# beaglebone_rotor_control_cape.net
KiCad netlist of a schematic drawn in EAGLE
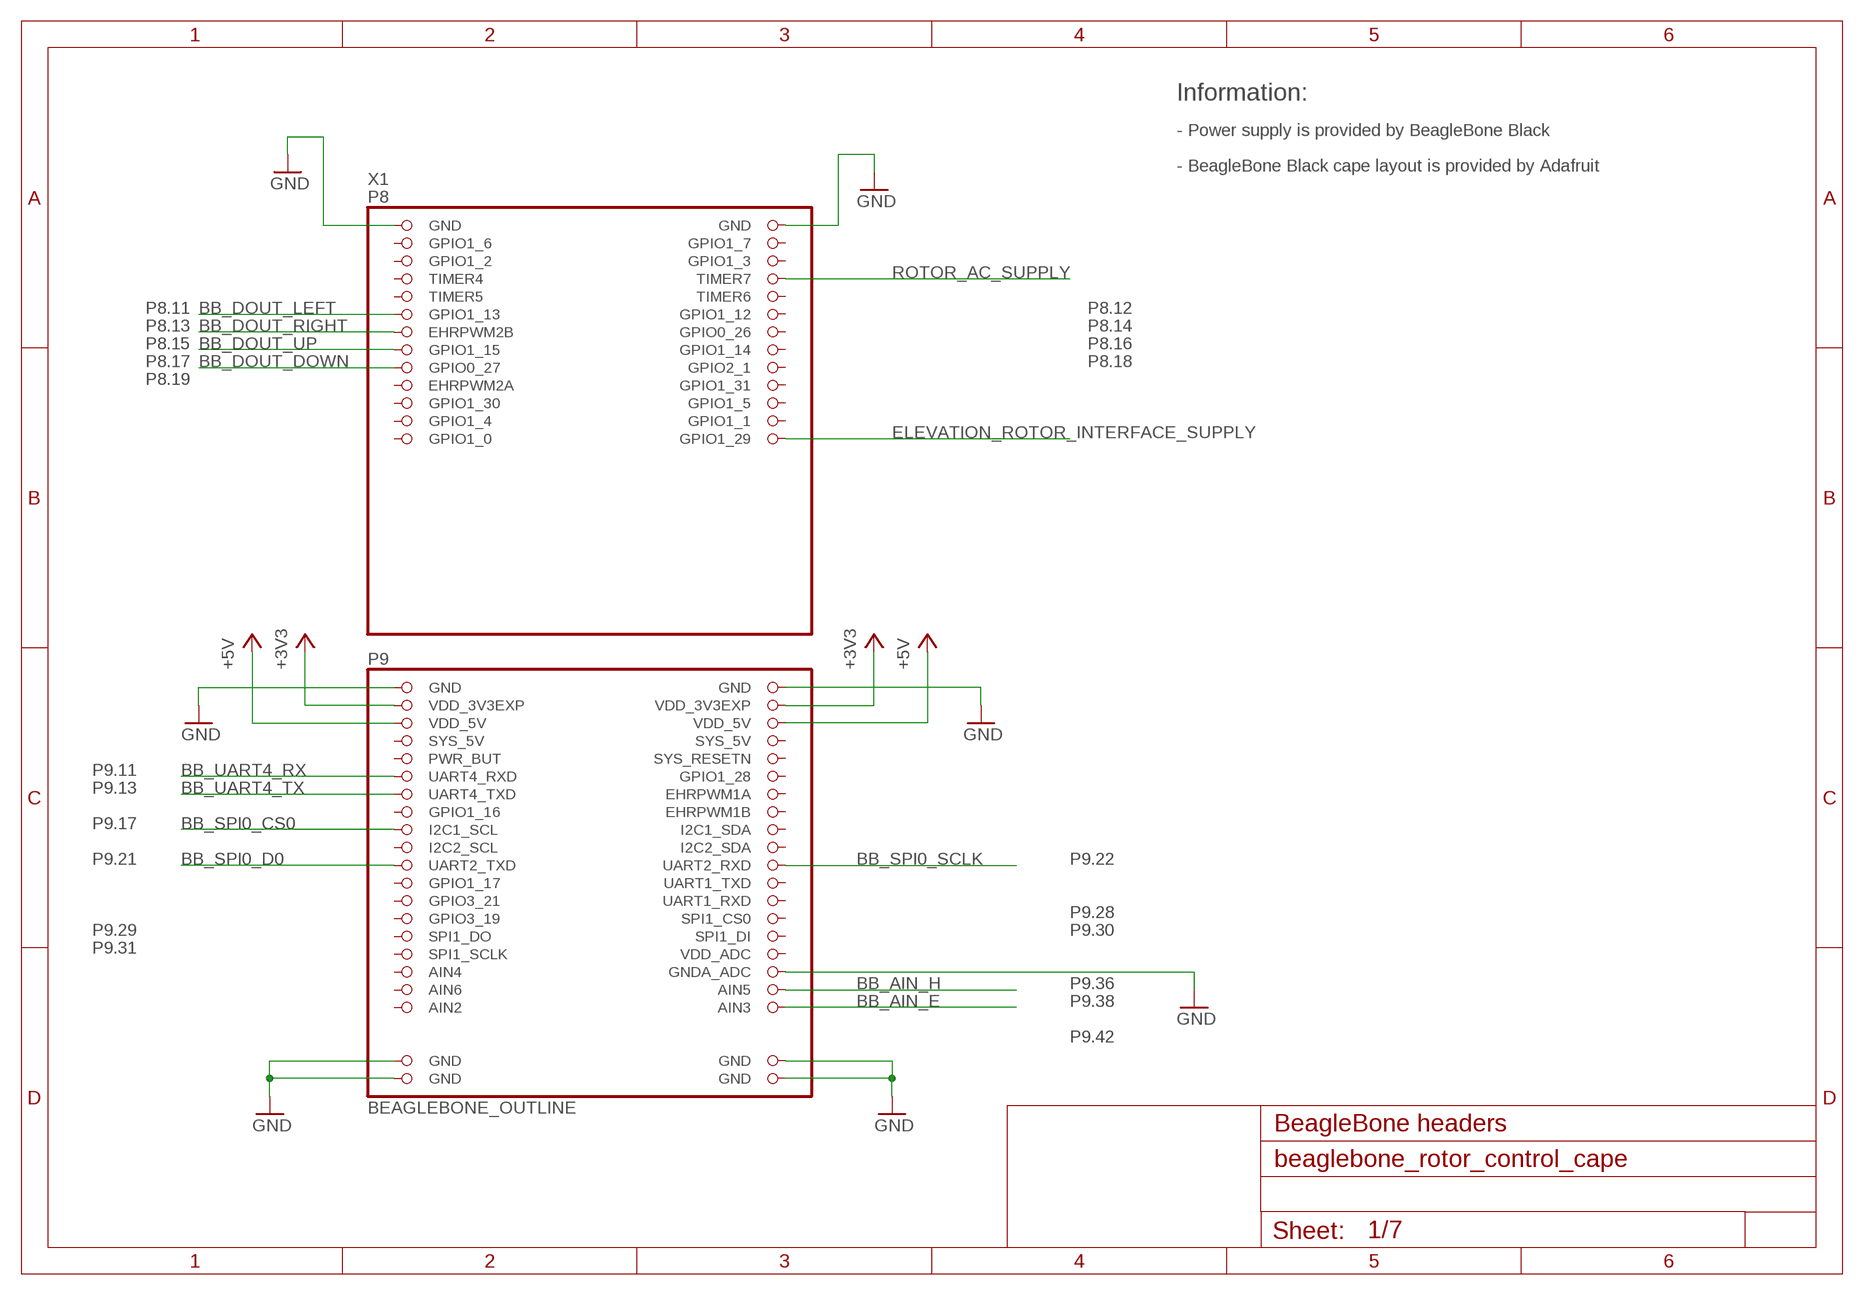
[diagram p0: schematic, sheet 1]
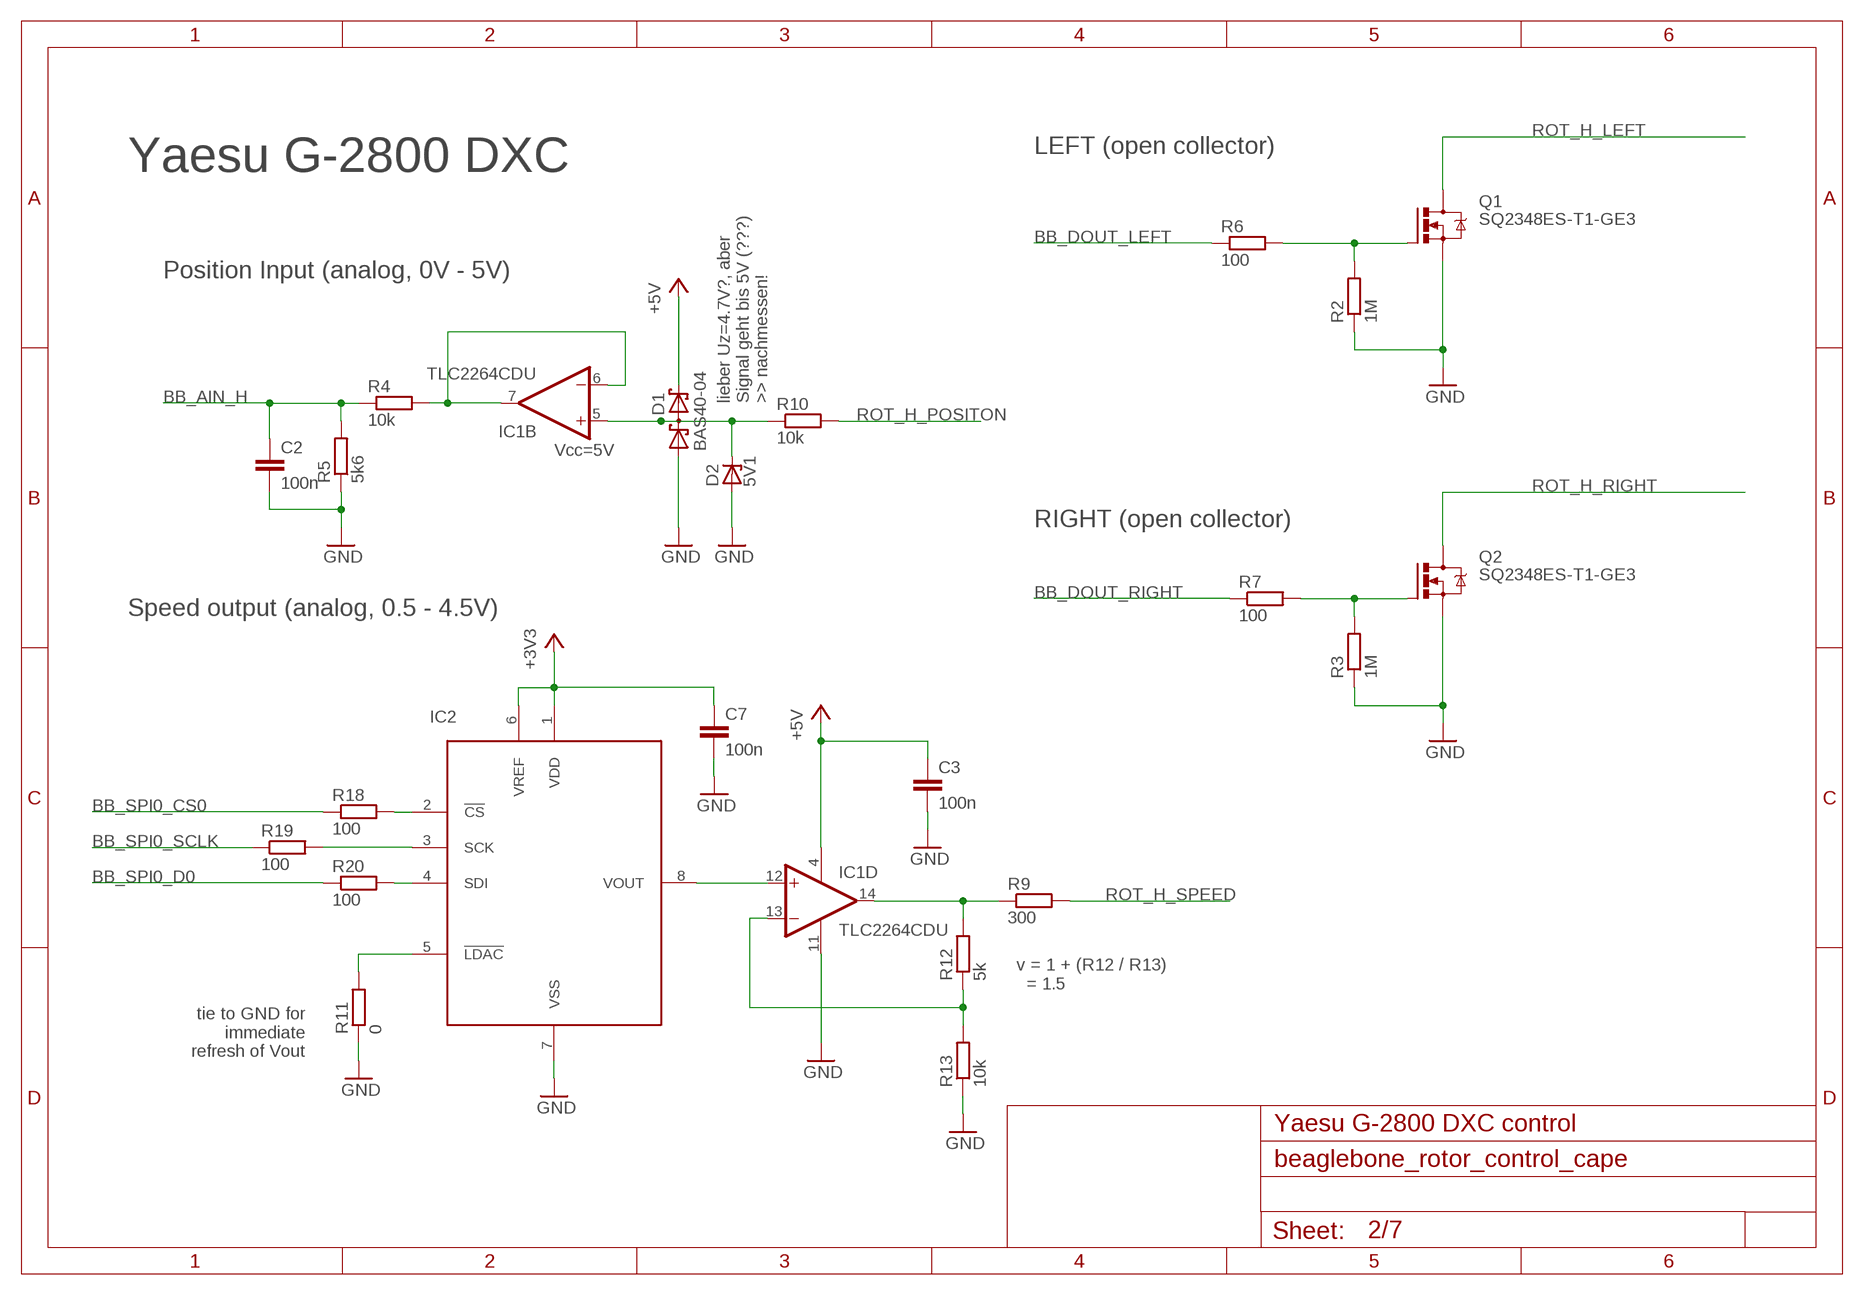
[diagram p1: schematic, sheet 2]
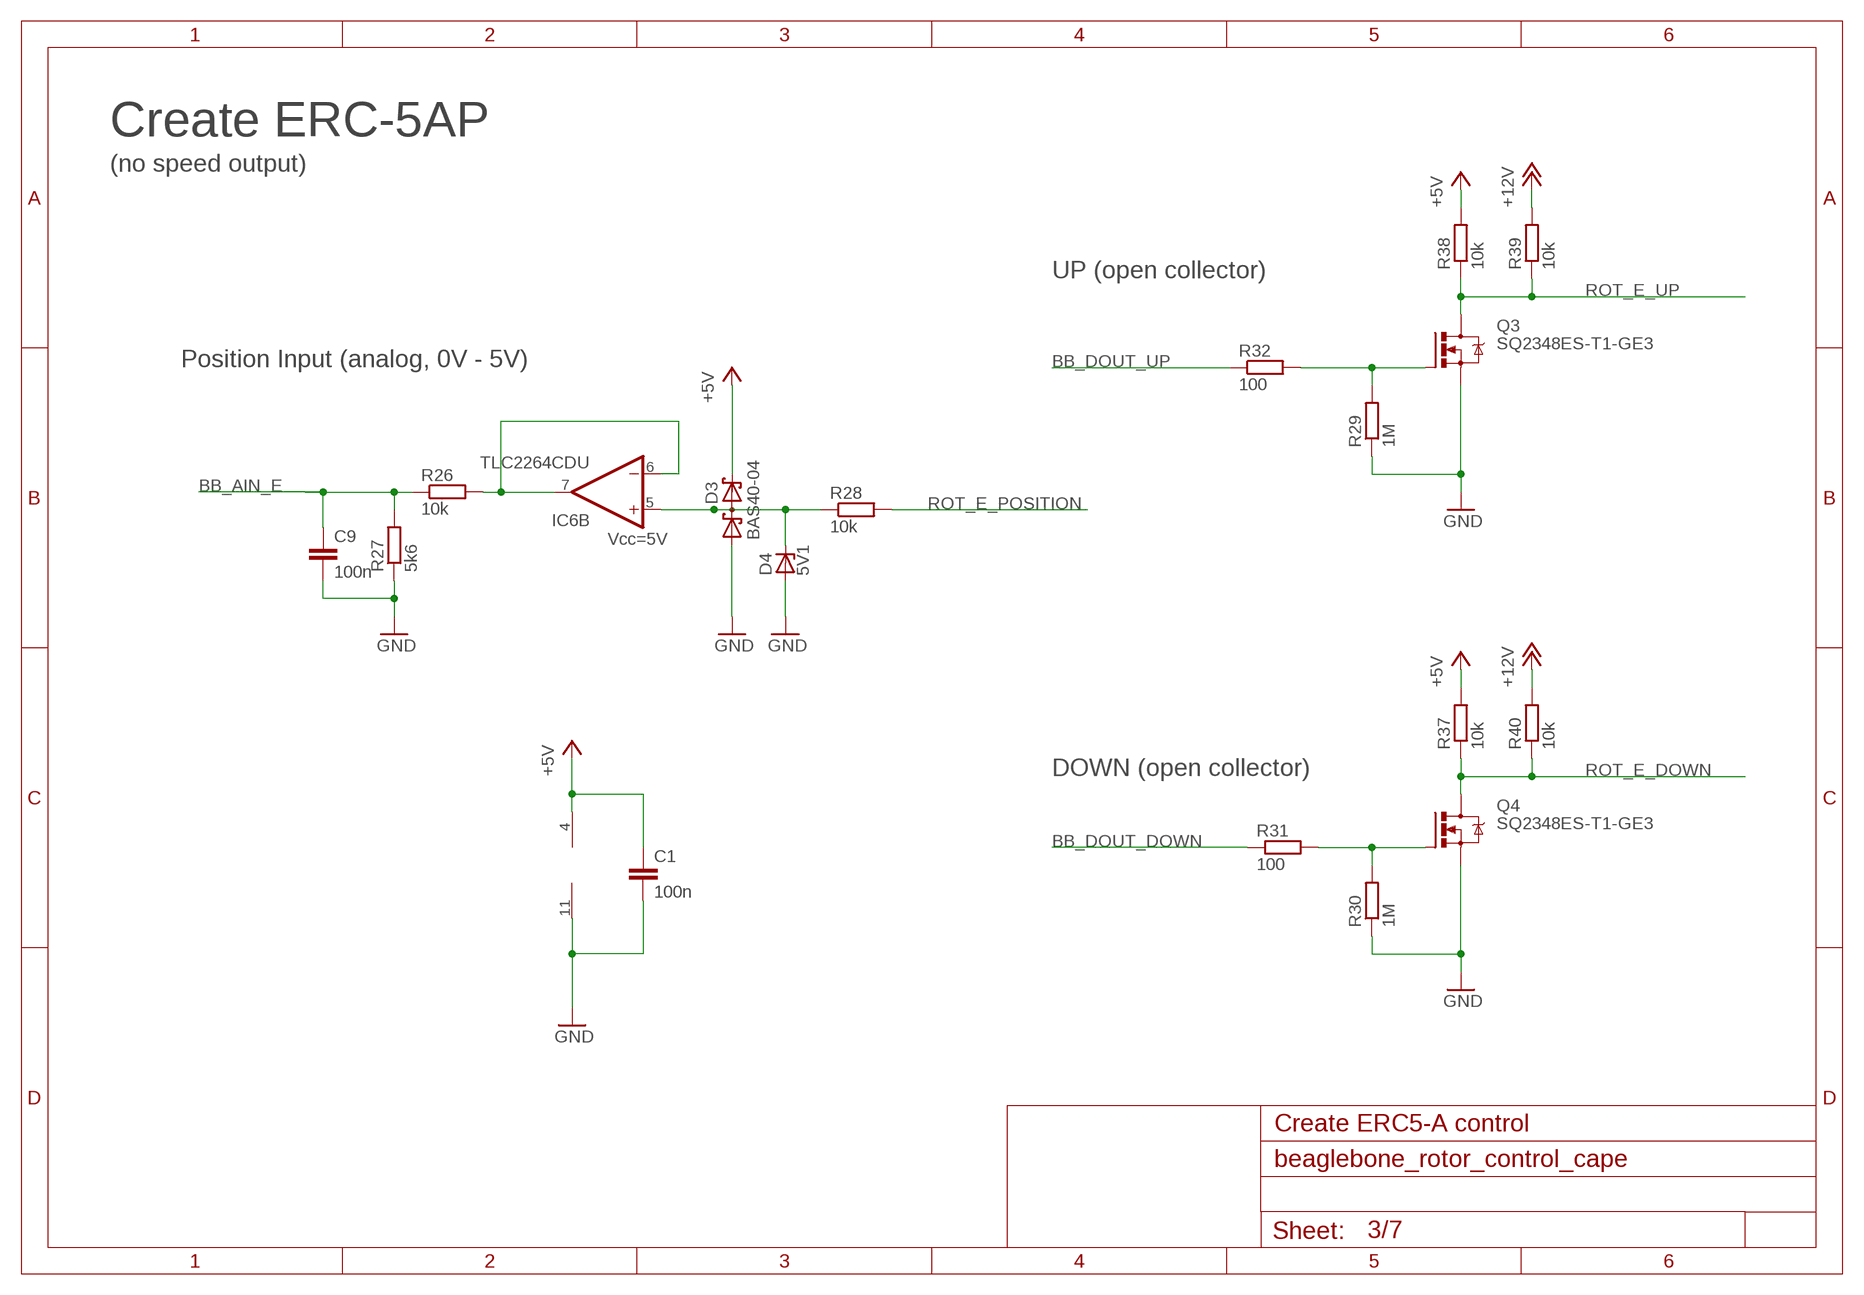
[diagram p2: schematic, sheet 3]
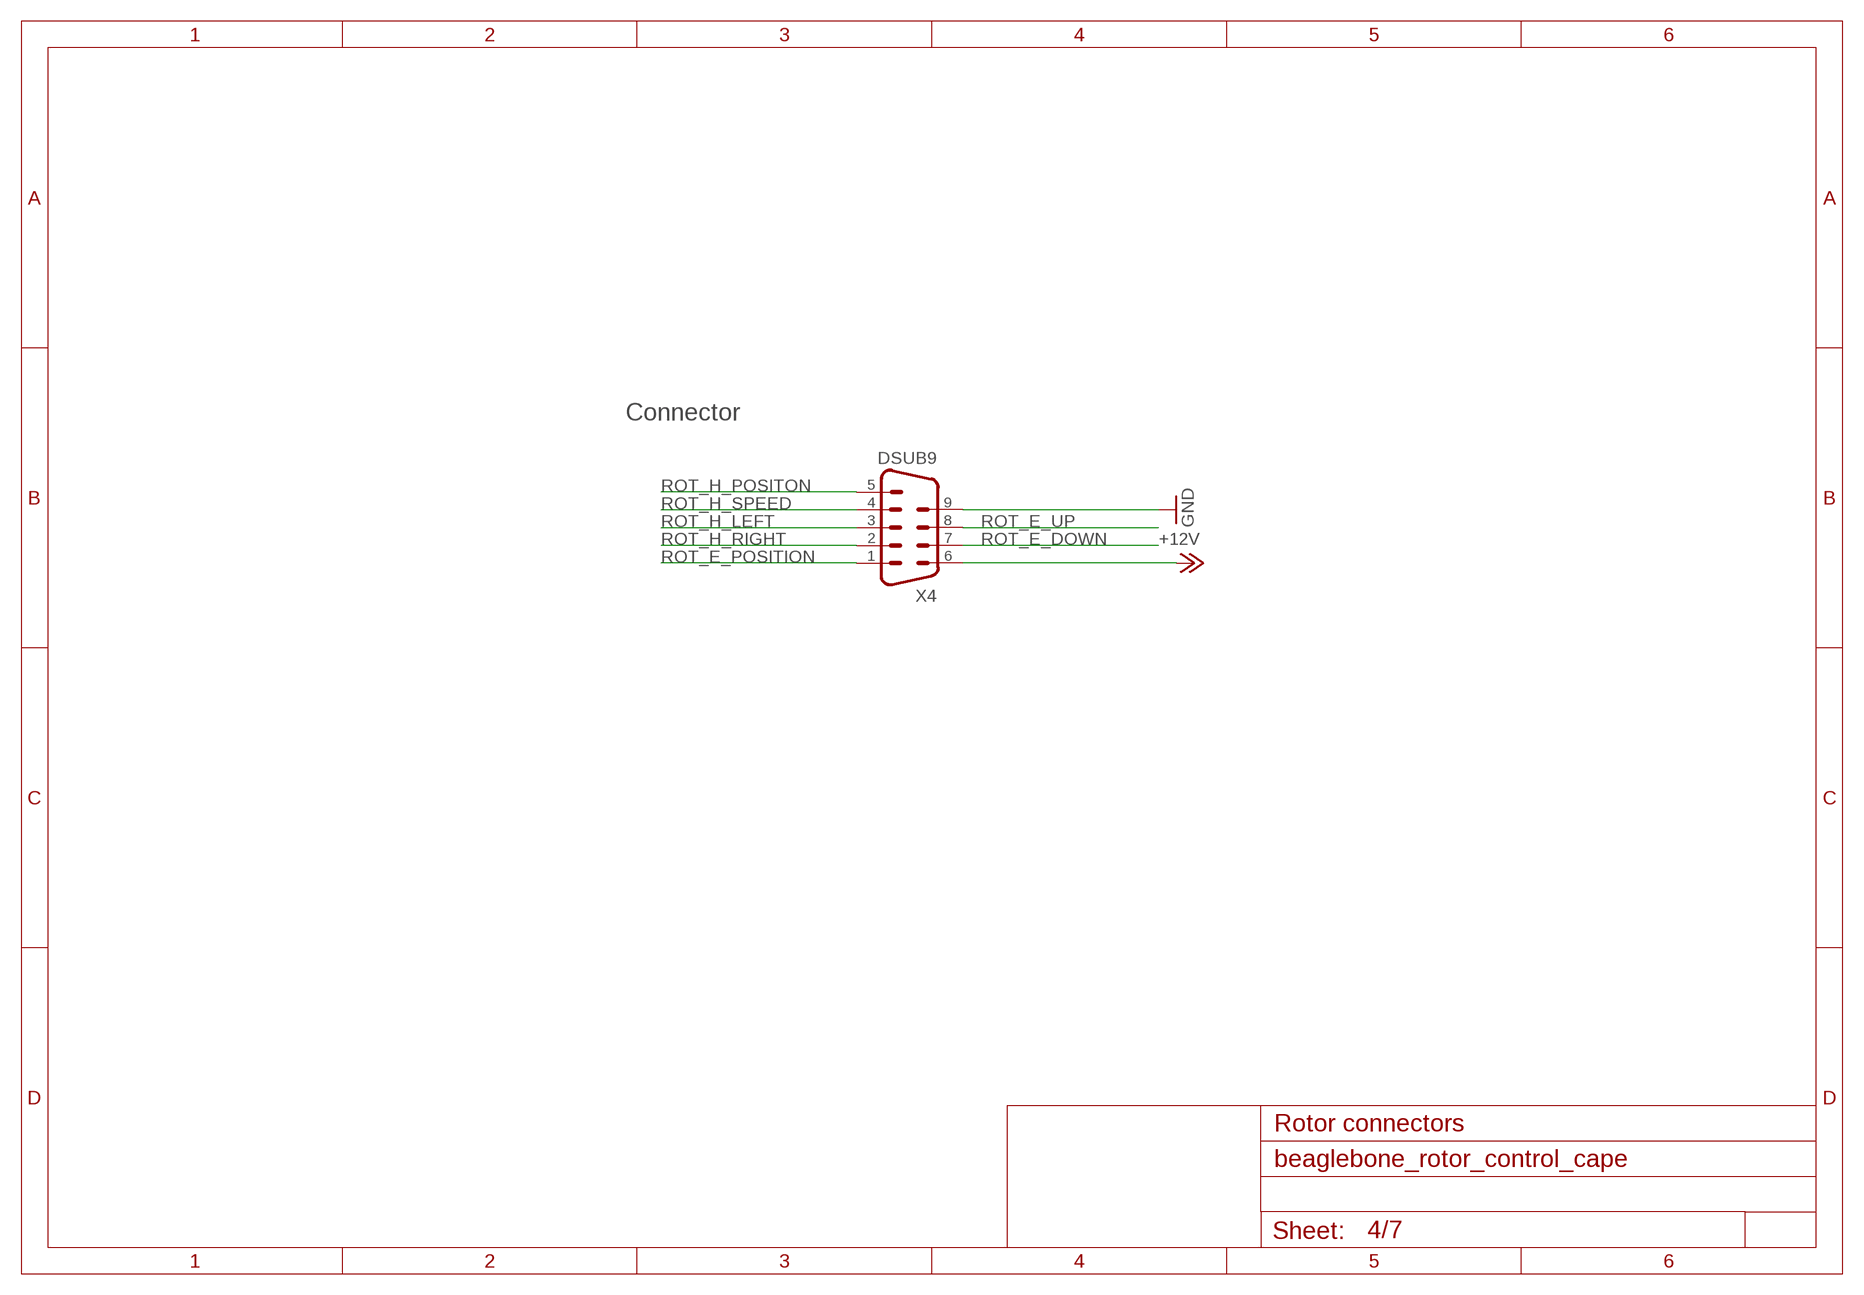
[diagram p3: schematic, sheet 4]
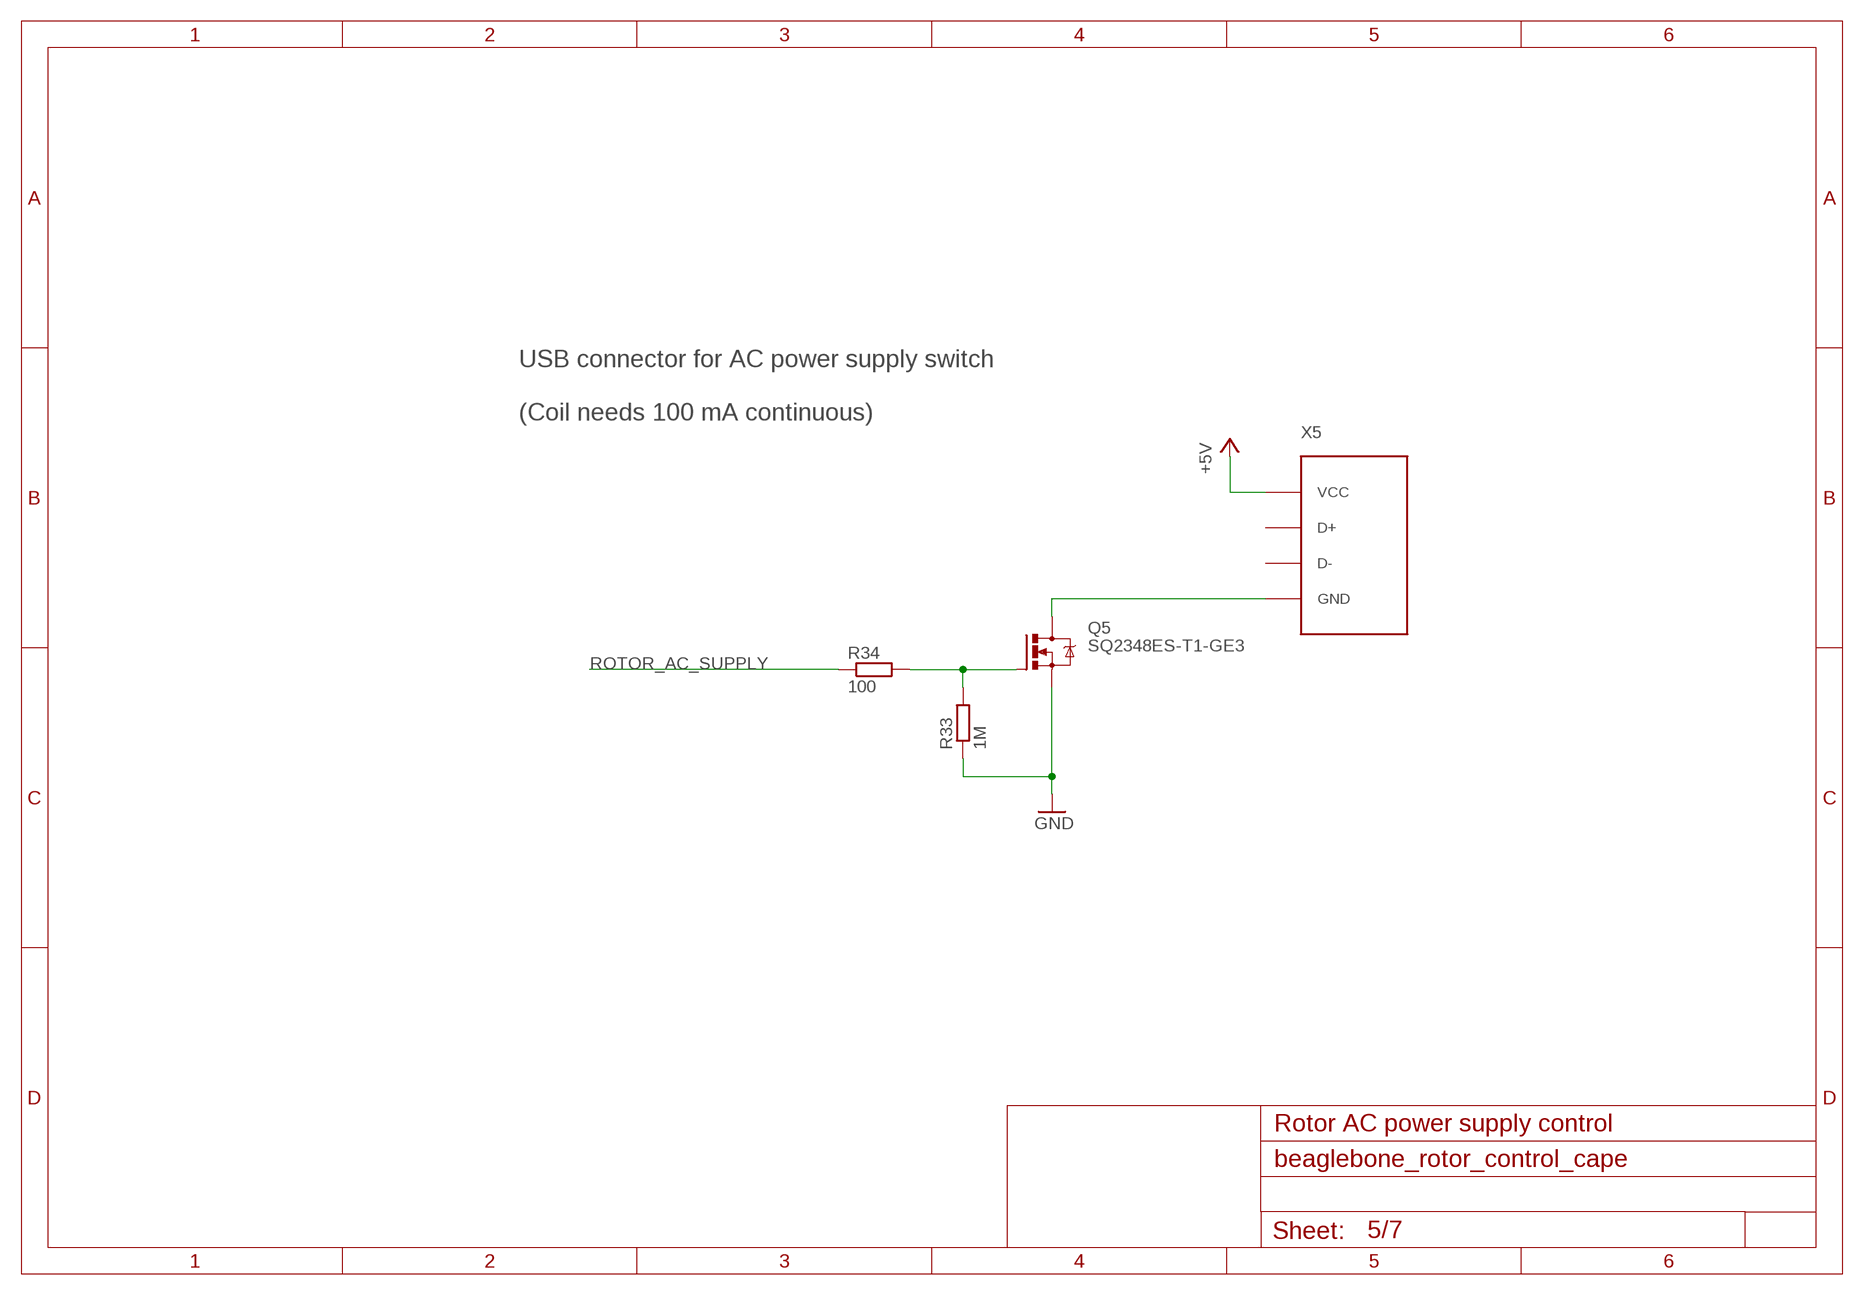
[diagram p4: schematic, sheet 5]
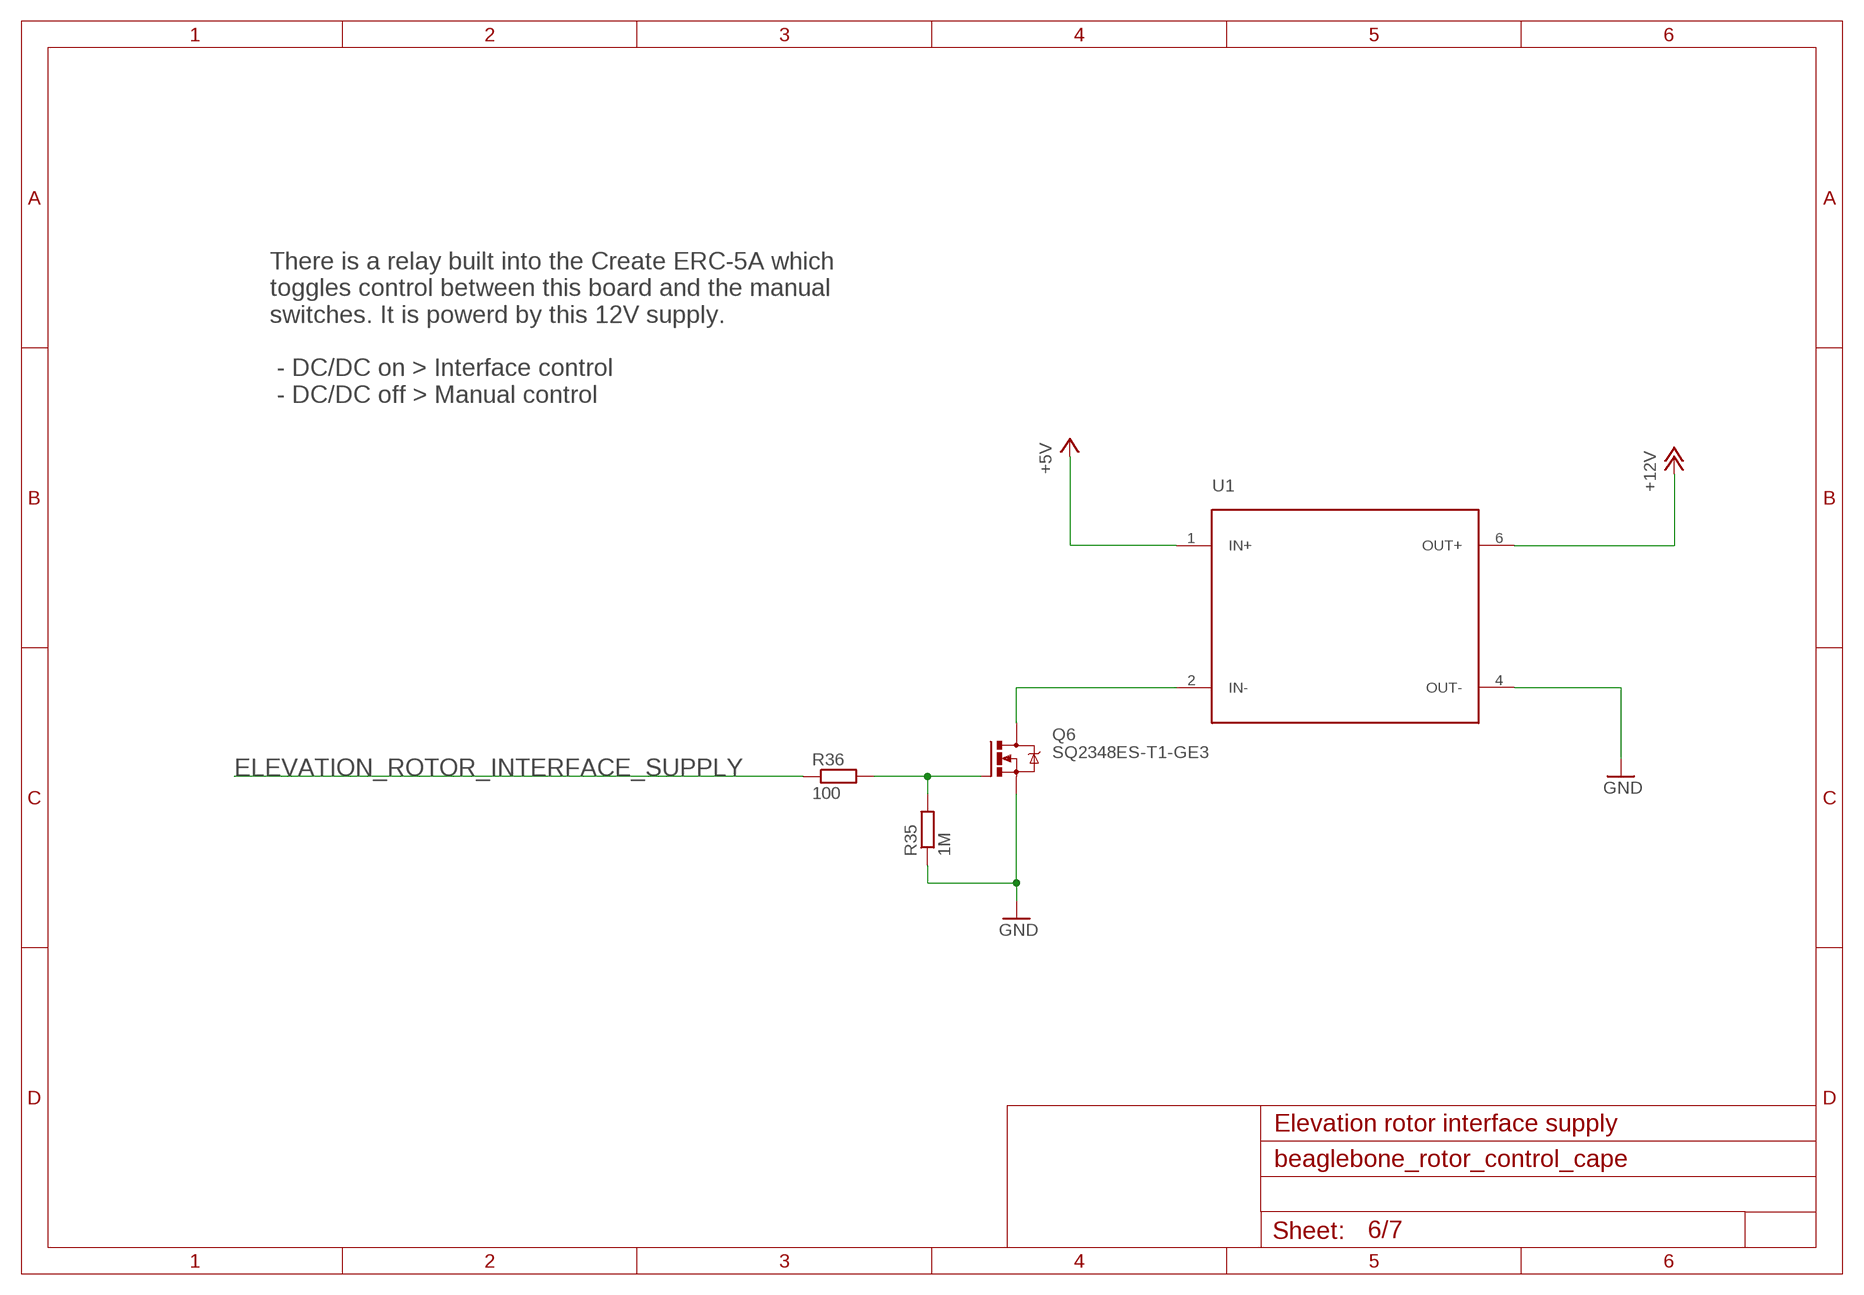
[diagram p5: schematic, sheet 6]
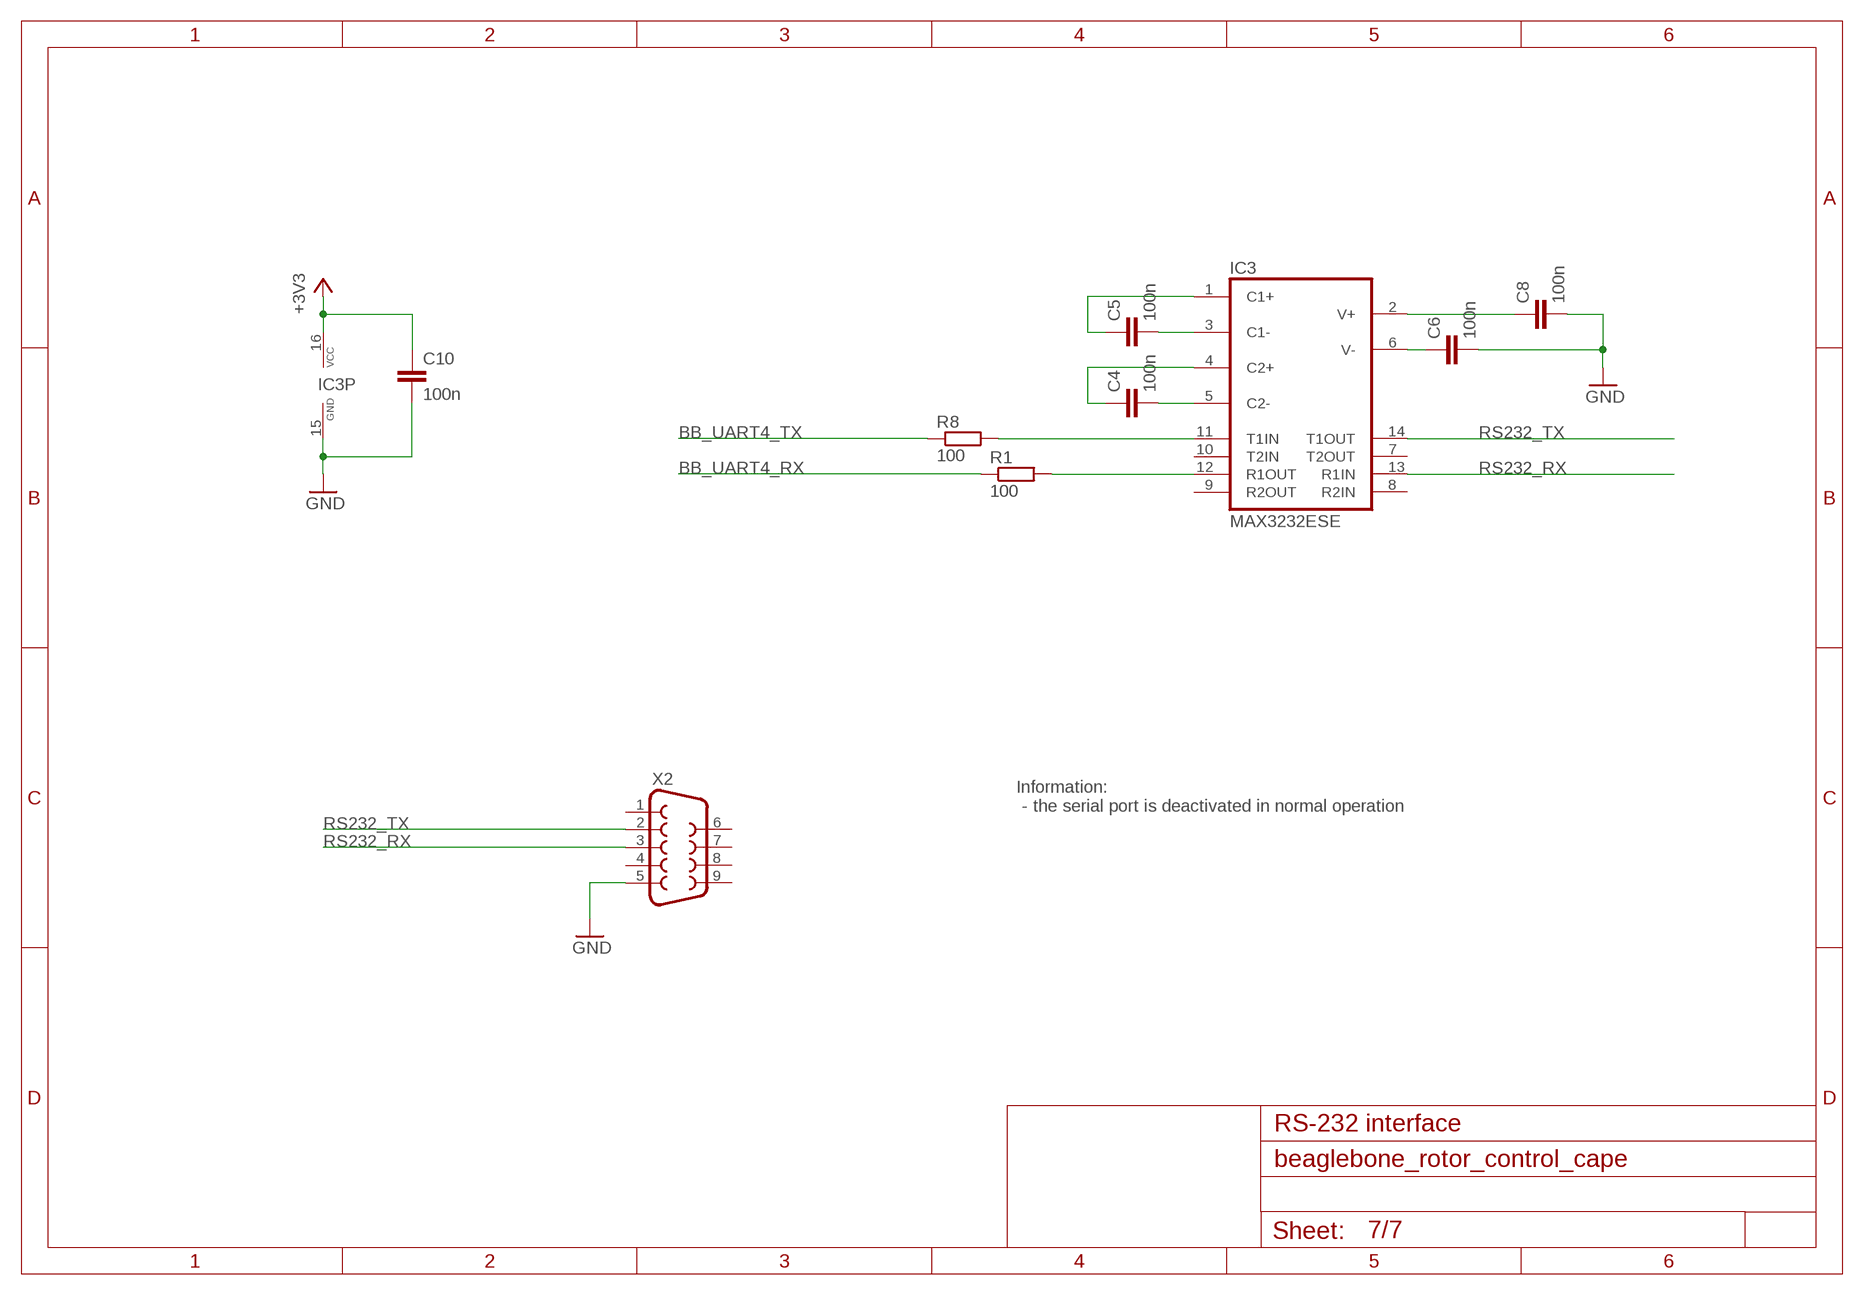
[diagram p6: schematic, sheet 7]

(export (version "E")
  (design (tool "Eeschema 10.0.6"))
  (components
    (comp (ref "C4")
      (value "100n")
      (footprint "eagle-import:C0603")
      (libsource (lib "eagle-import") (part "C-EUC0603"))
    )
    (comp (ref "C5")
      (value "100n")
      (footprint "eagle-import:C0603")
      (libsource (lib "eagle-import") (part "C-EUC0603"))
    )
    (comp (ref "C6")
      (value "100n")
      (footprint "eagle-import:C0603")
      (libsource (lib "eagle-import") (part "C-EUC0603"))
    )
    (comp (ref "C8")
      (value "100n")
      (footprint "eagle-import:C0603")
      (libsource (lib "eagle-import") (part "C-EUC0603"))
    )
    (comp (ref "C10")
      (value "100n")
      (footprint "eagle-import:C0603")
      (libsource (lib "eagle-import") (part "C-EUC0603"))
    )
    (comp (ref "IC3")
      (value "MAX3232ESE")
      (footprint "eagle-import:SO16")
      (fields (field (name "MF") "MAXIM"))
      (libsource (lib "eagle-import") (part "MAX3232SEE"))
    )
    (comp (ref "R1")
      (value "100")
      (footprint "eagle-import:R0805")
      (libsource (lib "eagle-import") (part "R-EU_R0805"))
    )
    (comp (ref "R8")
      (value "100")
      (footprint "eagle-import:R0805")
      (libsource (lib "eagle-import") (part "R-EU_R0805"))
    )
    (comp (ref "X2")
      (value "F09VP")
      (footprint "eagle-import:F09VP")
      (libsource (lib "eagle-import") (part "F09VP"))
    )
    (comp (ref "Q5")
      (value "SQ2348ES-T1-GE3")
      (footprint "eagle-import:SOT23")
      (libsource (lib "eagle-import") (part "SQ2348ES-T1-GE3"))
    )
    (comp (ref "R33")
      (value "1M")
      (footprint "eagle-import:R0805")
      (libsource (lib "eagle-import") (part "R-EU_R0805"))
    )
    (comp (ref "R34")
      (value "100")
      (footprint "eagle-import:R0805")
      (libsource (lib "eagle-import") (part "R-EU_R0805"))
    )
    (comp (ref "X5")
      (value "USBDEV")
      (footprint "eagle-import:USB")
      (libsource (lib "eagle-import") (part "USBDEV"))
    )
    (comp (ref "C2")
      (value "100n")
      (footprint "eagle-import:C0603")
      (libsource (lib "eagle-import") (part "C-EUC0603"))
    )
    (comp (ref "C3")
      (value "100n")
      (footprint "eagle-import:C0603")
      (libsource (lib "eagle-import") (part "C-EUC0603"))
    )
    (comp (ref "C7")
      (value "100n")
      (footprint "eagle-import:C0603")
      (libsource (lib "eagle-import") (part "C-EUC0603"))
    )
    (comp (ref "D1")
      (value "BAS40-04")
      (footprint "eagle-import:SOT23")
      (libsource (lib "eagle-import") (part "BAS40-04"))
    )
    (comp (ref "D2")
      (value "5V1")
      (footprint "eagle-import:SOT23")
      (libsource (lib "eagle-import") (part "ZENER-DIODESOT23"))
    )
    (comp (ref "IC1")
      (value "TLC2264CDU")
      (footprint "eagle-import:SO14")
      (libsource (lib "eagle-import") (part "TLC2264CDU"))
    )
    (comp (ref "IC2")
      (value "MCP4901")
      (footprint "eagle-import:SO-08")
      (libsource (lib "eagle-import") (part "MCP4901"))
    )
    (comp (ref "Q1")
      (value "SQ2348ES-T1-GE3")
      (footprint "eagle-import:SOT23")
      (libsource (lib "eagle-import") (part "SQ2348ES-T1-GE3"))
    )
    (comp (ref "Q2")
      (value "SQ2348ES-T1-GE3")
      (footprint "eagle-import:SOT23")
      (libsource (lib "eagle-import") (part "SQ2348ES-T1-GE3"))
    )
    (comp (ref "R2")
      (value "1M")
      (footprint "eagle-import:R0805")
      (libsource (lib "eagle-import") (part "R-EU_R0805"))
    )
    (comp (ref "R3")
      (value "1M")
      (footprint "eagle-import:R0805")
      (libsource (lib "eagle-import") (part "R-EU_R0805"))
    )
    (comp (ref "R4")
      (value "10k")
      (footprint "eagle-import:R0805")
      (libsource (lib "eagle-import") (part "R-EU_R0805"))
    )
    (comp (ref "R5")
      (value "5k6")
      (footprint "eagle-import:R0805")
      (libsource (lib "eagle-import") (part "R-EU_R0805"))
    )
    (comp (ref "R6")
      (value "100")
      (footprint "eagle-import:R0805")
      (libsource (lib "eagle-import") (part "R-EU_R0805"))
    )
    (comp (ref "R7")
      (value "100")
      (footprint "eagle-import:R0805")
      (libsource (lib "eagle-import") (part "R-EU_R0805"))
    )
    (comp (ref "R9")
      (value "300")
      (footprint "eagle-import:R0805")
      (libsource (lib "eagle-import") (part "R-EU_R0805"))
    )
    (comp (ref "R10")
      (value "10k")
      (footprint "eagle-import:R0805")
      (libsource (lib "eagle-import") (part "R-EU_R0805"))
    )
    (comp (ref "R11")
      (value "0")
      (footprint "eagle-import:R0805")
      (libsource (lib "eagle-import") (part "R-EU_R0805"))
    )
    (comp (ref "R12")
      (value "5k")
      (footprint "eagle-import:R0805")
      (libsource (lib "eagle-import") (part "R-EU_R0805"))
    )
    (comp (ref "R13")
      (value "10k")
      (footprint "eagle-import:R0805")
      (libsource (lib "eagle-import") (part "R-EU_R0805"))
    )
    (comp (ref "R18")
      (value "100")
      (footprint "eagle-import:R0805")
      (libsource (lib "eagle-import") (part "R-EU_R0805"))
    )
    (comp (ref "R19")
      (value "100")
      (footprint "eagle-import:R0805")
      (libsource (lib "eagle-import") (part "R-EU_R0805"))
    )
    (comp (ref "R20")
      (value "100")
      (footprint "eagle-import:R0805")
      (libsource (lib "eagle-import") (part "R-EU_R0805"))
    )
    (comp (ref "X1")
      (value "BEAGLEBONE_OUTLINE")
      (footprint "eagle-import:BEAGLEBONE_SHIELD")
      (libsource (lib "eagle-import") (part "BEAGLEBONE_OUTLINE"))
    )
    (comp (ref "C1")
      (value "100n")
      (footprint "eagle-import:C0603")
      (libsource (lib "eagle-import") (part "C-EUC0603"))
    )
    (comp (ref "C9")
      (value "100n")
      (footprint "eagle-import:C0603")
      (libsource (lib "eagle-import") (part "C-EUC0603"))
    )
    (comp (ref "D3")
      (value "BAS40-04")
      (footprint "eagle-import:SOT23")
      (libsource (lib "eagle-import") (part "BAS40-04"))
    )
    (comp (ref "D4")
      (value "5V1")
      (footprint "eagle-import:SOT23")
      (libsource (lib "eagle-import") (part "ZENER-DIODESOT23"))
    )
    (comp (ref "IC6")
      (value "TLC2264CDU")
      (footprint "eagle-import:SO14")
      (libsource (lib "eagle-import") (part "TLC2264CDU"))
    )
    (comp (ref "Q3")
      (value "SQ2348ES-T1-GE3")
      (footprint "eagle-import:SOT23")
      (libsource (lib "eagle-import") (part "SQ2348ES-T1-GE3"))
    )
    (comp (ref "Q4")
      (value "SQ2348ES-T1-GE3")
      (footprint "eagle-import:SOT23")
      (libsource (lib "eagle-import") (part "SQ2348ES-T1-GE3"))
    )
    (comp (ref "R26")
      (value "10k")
      (footprint "eagle-import:R0805")
      (libsource (lib "eagle-import") (part "R-EU_R0805"))
    )
    (comp (ref "R27")
      (value "5k6")
      (footprint "eagle-import:R0805")
      (libsource (lib "eagle-import") (part "R-EU_R0805"))
    )
    (comp (ref "R28")
      (value "10k")
      (footprint "eagle-import:R0805")
      (libsource (lib "eagle-import") (part "R-EU_R0805"))
    )
    (comp (ref "R29")
      (value "1M")
      (footprint "eagle-import:R0805")
      (libsource (lib "eagle-import") (part "R-EU_R0805"))
    )
    (comp (ref "R30")
      (value "1M")
      (footprint "eagle-import:R0805")
      (libsource (lib "eagle-import") (part "R-EU_R0805"))
    )
    (comp (ref "R31")
      (value "100")
      (footprint "eagle-import:R0805")
      (libsource (lib "eagle-import") (part "R-EU_R0805"))
    )
    (comp (ref "R32")
      (value "100")
      (footprint "eagle-import:R0805")
      (libsource (lib "eagle-import") (part "R-EU_R0805"))
    )
    (comp (ref "R37")
      (value "10k")
      (footprint "eagle-import:R0805")
      (libsource (lib "eagle-import") (part "R-EU_R0805"))
    )
    (comp (ref "R38")
      (value "10k")
      (footprint "eagle-import:R0805")
      (libsource (lib "eagle-import") (part "R-EU_R0805"))
    )
    (comp (ref "R39")
      (value "10k")
      (footprint "eagle-import:R0805")
      (libsource (lib "eagle-import") (part "R-EU_R0805"))
    )
    (comp (ref "R40")
      (value "10k")
      (footprint "eagle-import:R0805")
      (libsource (lib "eagle-import") (part "R-EU_R0805"))
    )
    (comp (ref "X4")
      (value "DSUB9")
      (footprint "eagle-import:DSUB9")
      (libsource (lib "eagle-import") (part "DSUB9"))
    )
    (comp (ref "Q6")
      (value "SQ2348ES-T1-GE3")
      (footprint "eagle-import:SOT23")
      (libsource (lib "eagle-import") (part "SQ2348ES-T1-GE3"))
    )
    (comp (ref "R35")
      (value "1M")
      (footprint "eagle-import:R0805")
      (libsource (lib "eagle-import") (part "R-EU_R0805"))
    )
    (comp (ref "R36")
      (value "100")
      (footprint "eagle-import:R0805")
      (libsource (lib "eagle-import") (part "R-EU_R0805"))
    )
    (comp (ref "U1")
      (value "TMH0512S")
      (footprint "eagle-import:SIP")
      (libsource (lib "eagle-import") (part "TMH0512S"))
    )
  )
  (nets
    (net (code "1") (name "+3V3") (class "Default")
      (node (ref "C10") (pin "1") (pinfunction "1_1") (pintype "passive"))
      (node (ref "C7") (pin "1") (pinfunction "1_1") (pintype "passive"))
      (node (ref "IC2") (pin "1") (pinfunction "VDD_1") (pintype "bidirectional"))
      (node (ref "IC2") (pin "6") (pinfunction "VREF_6") (pintype "bidirectional"))
      (node (ref "IC3") (pin "16") (pinfunction "VCC_16") (pintype "power_in"))
      (node (ref "X1") (pin "49") (pinfunction "VDD_3V3EXP_49") (pintype "power_in"))
      (node (ref "X1") (pin "50") (pinfunction "VDD_3V3EXP_50") (pintype "power_in"))
    )
    (net (code "2") (name "+5V") (class "Default")
      (node (ref "C1") (pin "1") (pinfunction "1_1") (pintype "passive"))
      (node (ref "C3") (pin "1") (pinfunction "1_1") (pintype "passive"))
      (node (ref "D1") (pin "2") (pinfunction "C2_2") (pintype "passive"))
      (node (ref "D3") (pin "2") (pinfunction "C2_2") (pintype "passive"))
      (node (ref "IC1") (pin "4") (pinfunction "V+_4") (pintype "power_in"))
      (node (ref "IC6") (pin "4") (pinfunction "V+_4") (pintype "power_in"))
      (node (ref "R37") (pin "2") (pinfunction "2_2") (pintype "passive"))
      (node (ref "R38") (pin "2") (pinfunction "2_2") (pintype "passive"))
      (node (ref "U1") (pin "1") (pinfunction "IN+_1") (pintype "bidirectional"))
      (node (ref "X1") (pin "51") (pinfunction "VDD_5V_51") (pintype "power_in"))
      (node (ref "X1") (pin "52") (pinfunction "VDD_5V_52") (pintype "power_in"))
      (node (ref "X5") (pin "1-VCC") (pinfunction "VCC_1-VCC") (pintype "bidirectional"))
    )
    (net (code "3") (name "+12V") (class "Default")
      (node (ref "R39") (pin "2") (pinfunction "2_2") (pintype "passive"))
      (node (ref "R40") (pin "2") (pinfunction "2_2") (pintype "passive"))
      (node (ref "U1") (pin "6") (pinfunction "OUT+_6") (pintype "bidirectional"))
      (node (ref "X4") (pin "6") (pinfunction "6_6") (pintype "passive"))
    )
    (net (code "4") (name "BB_AIN_E") (class "Default")
      (node (ref "C9") (pin "1") (pinfunction "1_1") (pintype "passive"))
      (node (ref "R26") (pin "1") (pinfunction "1_1") (pintype "passive"))
      (node (ref "R27") (pin "2") (pinfunction "2_2") (pintype "passive"))
      (node (ref "X1") (pin "84") (pinfunction "AIN3_84") (pintype "passive"))
    )
    (net (code "5") (name "BB_AIN_H") (class "Default")
      (node (ref "C2") (pin "1") (pinfunction "1_1") (pintype "passive"))
      (node (ref "R4") (pin "1") (pinfunction "1_1") (pintype "passive"))
      (node (ref "R5") (pin "2") (pinfunction "2_2") (pintype "passive"))
      (node (ref "X1") (pin "82") (pinfunction "AIN5_82") (pintype "passive"))
    )
    (net (code "6") (name "BB_DOUT_DOWN") (class "Default")
      (node (ref "R31") (pin "1") (pinfunction "1_1") (pintype "passive"))
      (node (ref "X1") (pin "17") (pinfunction "GPIO0_27_17") (pintype "passive"))
    )
    (net (code "7") (name "BB_DOUT_LEFT") (class "Default")
      (node (ref "R6") (pin "1") (pinfunction "1_1") (pintype "passive"))
      (node (ref "X1") (pin "11") (pinfunction "GPIO1_13_11") (pintype "passive"))
    )
    (net (code "8") (name "BB_DOUT_RIGHT") (class "Default")
      (node (ref "R7") (pin "1") (pinfunction "1_1") (pintype "passive"))
      (node (ref "X1") (pin "13") (pinfunction "EHRPWM2B_13") (pintype "passive"))
    )
    (net (code "9") (name "BB_DOUT_UP") (class "Default")
      (node (ref "R32") (pin "1") (pinfunction "1_1") (pintype "passive"))
      (node (ref "X1") (pin "15") (pinfunction "GPIO1_15_15") (pintype "passive"))
    )
    (net (code "10") (name "BB_SPI0_CS0") (class "Default")
      (node (ref "R18") (pin "1") (pinfunction "1_1") (pintype "passive"))
      (node (ref "X1") (pin "63") (pinfunction "I2C1_SCL_63") (pintype "passive"))
    )
    (net (code "11") (name "BB_SPI0_D0") (class "Default")
      (node (ref "R20") (pin "1") (pinfunction "1_1") (pintype "passive"))
      (node (ref "X1") (pin "67") (pinfunction "UART2_TXD_67") (pintype "passive"))
    )
    (net (code "12") (name "BB_SPI0_SCLK") (class "Default")
      (node (ref "R19") (pin "1") (pinfunction "1_1") (pintype "passive"))
      (node (ref "X1") (pin "68") (pinfunction "UART2_RXD_68") (pintype "passive"))
    )
    (net (code "13") (name "BB_UART4_RX") (class "Default")
      (node (ref "R1") (pin "1") (pinfunction "1_1") (pintype "passive"))
      (node (ref "X1") (pin "57") (pinfunction "UART4_RXD_57") (pintype "passive"))
    )
    (net (code "14") (name "BB_UART4_TX") (class "Default")
      (node (ref "R8") (pin "1") (pinfunction "1_1") (pintype "passive"))
      (node (ref "X1") (pin "59") (pinfunction "UART4_TXD_59") (pintype "passive"))
    )
    (net (code "15") (name "ELEVATION_ROTOR_INTERFACE_SUPPLY") (class "Default")
      (node (ref "R36") (pin "1") (pinfunction "1_1") (pintype "passive"))
      (node (ref "X1") (pin "26") (pinfunction "GPIO1_29_26") (pintype "passive"))
    )
    (net (code "16") (name "GND") (class "Default")
      (node (ref "C1") (pin "2") (pinfunction "2_2") (pintype "passive"))
      (node (ref "C10") (pin "2") (pinfunction "2_2") (pintype "passive"))
      (node (ref "C2") (pin "2") (pinfunction "2_2") (pintype "passive"))
      (node (ref "C3") (pin "2") (pinfunction "2_2") (pintype "passive"))
      (node (ref "C6") (pin "2") (pinfunction "2_2") (pintype "passive"))
      (node (ref "C7") (pin "2") (pinfunction "2_2") (pintype "passive"))
      (node (ref "C8") (pin "2") (pinfunction "2_2") (pintype "passive"))
      (node (ref "C9") (pin "2") (pinfunction "2_2") (pintype "passive"))
      (node (ref "D1") (pin "1") (pinfunction "A1_1") (pintype "passive"))
      (node (ref "D2") (pin "1") (pinfunction "A_1") (pintype "passive"))
      (node (ref "D3") (pin "1") (pinfunction "A1_1") (pintype "passive"))
      (node (ref "D4") (pin "1") (pinfunction "A_1") (pintype "passive"))
      (node (ref "IC1") (pin "11") (pinfunction "V-_11") (pintype "power_in"))
      (node (ref "IC2") (pin "7") (pinfunction "VSS_7") (pintype "bidirectional"))
      (node (ref "IC3") (pin "15") (pinfunction "GND_15") (pintype "power_in"))
      (node (ref "IC6") (pin "11") (pinfunction "V-_11") (pintype "power_in"))
      (node (ref "Q1") (pin "2") (pinfunction "S_2") (pintype "passive"))
      (node (ref "Q2") (pin "2") (pinfunction "S_2") (pintype "passive"))
      (node (ref "Q3") (pin "2") (pinfunction "S_2") (pintype "passive"))
      (node (ref "Q4") (pin "2") (pinfunction "S_2") (pintype "passive"))
      (node (ref "Q5") (pin "2") (pinfunction "S_2") (pintype "passive"))
      (node (ref "Q6") (pin "2") (pinfunction "S_2") (pintype "passive"))
      (node (ref "R11") (pin "1") (pinfunction "1_1") (pintype "passive"))
      (node (ref "R13") (pin "1") (pinfunction "1_1") (pintype "passive"))
      (node (ref "R2") (pin "1") (pinfunction "1_1") (pintype "passive"))
      (node (ref "R27") (pin "1") (pinfunction "1_1") (pintype "passive"))
      (node (ref "R29") (pin "1") (pinfunction "1_1") (pintype "passive"))
      (node (ref "R3") (pin "1") (pinfunction "1_1") (pintype "passive"))
      (node (ref "R30") (pin "1") (pinfunction "1_1") (pintype "passive"))
      (node (ref "R33") (pin "1") (pinfunction "1_1") (pintype "passive"))
      (node (ref "R35") (pin "1") (pinfunction "1_1") (pintype "passive"))
      (node (ref "R5") (pin "1") (pinfunction "1_1") (pintype "passive"))
      (node (ref "U1") (pin "4") (pinfunction "OUT-_4") (pintype "bidirectional"))
      (node (ref "X1") (pin "1") (pinfunction "GND_1") (pintype "power_in"))
      (node (ref "X1") (pin "2") (pinfunction "GND_2") (pintype "power_in"))
      (node (ref "X1") (pin "47") (pinfunction "GND_47") (pintype "power_in"))
      (node (ref "X1") (pin "48") (pinfunction "GND_48") (pintype "power_in"))
      (node (ref "X1") (pin "80") (pinfunction "GNDA_ADC_80") (pintype "passive"))
      (node (ref "X1") (pin "89") (pinfunction "GND_89") (pintype "power_in"))
      (node (ref "X1") (pin "90") (pinfunction "GND_90") (pintype "power_in"))
      (node (ref "X1") (pin "91") (pinfunction "GND_91") (pintype "power_in"))
      (node (ref "X1") (pin "92") (pinfunction "GND_92") (pintype "power_in"))
      (node (ref "X2") (pin "5") (pinfunction "5_5") (pintype "passive"))
      (node (ref "X4") (pin "9") (pinfunction "9_9") (pintype "passive"))
    )
    (net (code "17") (name "Net-(D1-C1A2)") (class "Default")
      (node (ref "D1") (pin "3") (pinfunction "C1A2_3") (pintype "passive"))
      (node (ref "D2") (pin "3") (pinfunction "C_3") (pintype "passive"))
      (node (ref "IC1") (pin "5") (pinfunction "+IN_5") (pintype "input"))
      (node (ref "R10") (pin "1") (pinfunction "1_1") (pintype "passive"))
    )
    (net (code "18") (name "Net-(D3-C1A2)") (class "Default")
      (node (ref "D3") (pin "3") (pinfunction "C1A2_3") (pintype "passive"))
      (node (ref "D4") (pin "3") (pinfunction "C_3") (pintype "passive"))
      (node (ref "IC6") (pin "5") (pinfunction "+IN_5") (pintype "input"))
      (node (ref "R28") (pin "1") (pinfunction "1_1") (pintype "passive"))
    )
    (net (code "19") (name "Net-(IC1B--IN)") (class "Default")
      (node (ref "IC1") (pin "6") (pinfunction "-IN_6") (pintype "input"))
      (node (ref "IC1") (pin "7") (pinfunction "OUT_7") (pintype "output"))
      (node (ref "R4") (pin "2") (pinfunction "2_2") (pintype "passive"))
    )
    (net (code "20") (name "Net-(IC1D-+IN)") (class "Default")
      (node (ref "IC1") (pin "12") (pinfunction "+IN_12") (pintype "input"))
      (node (ref "IC2") (pin "8") (pinfunction "VOUT_8") (pintype "bidirectional"))
    )
    (net (code "21") (name "Net-(IC1D--IN)") (class "Default")
      (node (ref "IC1") (pin "13") (pinfunction "-IN_13") (pintype "input"))
      (node (ref "R12") (pin "1") (pinfunction "1_1") (pintype "passive"))
      (node (ref "R13") (pin "2") (pinfunction "2_2") (pintype "passive"))
    )
    (net (code "22") (name "Net-(IC1D-OUT)") (class "Default")
      (node (ref "IC1") (pin "14") (pinfunction "OUT_14") (pintype "output"))
      (node (ref "R12") (pin "2") (pinfunction "2_2") (pintype "passive"))
      (node (ref "R9") (pin "1") (pinfunction "1_1") (pintype "passive"))
    )
    (net (code "23") (name "Net-(IC2-SCK)") (class "Default")
      (node (ref "IC2") (pin "3") (pinfunction "SCK_3") (pintype "bidirectional"))
      (node (ref "R19") (pin "2") (pinfunction "2_2") (pintype "passive"))
    )
    (net (code "24") (name "Net-(IC2-SDI)") (class "Default")
      (node (ref "IC2") (pin "4") (pinfunction "SDI_4") (pintype "bidirectional"))
      (node (ref "R20") (pin "2") (pinfunction "2_2") (pintype "passive"))
    )
    (net (code "25") (name "Net-(IC2-~{CS})") (class "Default")
      (node (ref "IC2") (pin "2") (pinfunction "~{CS}_2") (pintype "bidirectional"))
      (node (ref "R18") (pin "2") (pinfunction "2_2") (pintype "passive"))
    )
    (net (code "26") (name "Net-(IC2-~{LDAC})") (class "Default")
      (node (ref "IC2") (pin "5") (pinfunction "~{LDAC}_5") (pintype "bidirectional"))
      (node (ref "R11") (pin "2") (pinfunction "2_2") (pintype "passive"))
    )
    (net (code "27") (name "Net-(IC3A-C1+)") (class "Default")
      (node (ref "C5") (pin "1") (pinfunction "1_1") (pintype "passive"))
      (node (ref "IC3") (pin "1") (pinfunction "C1+_1") (pintype "bidirectional"))
    )
    (net (code "28") (name "Net-(IC3A-C1-)") (class "Default")
      (node (ref "C5") (pin "2") (pinfunction "2_2") (pintype "passive"))
      (node (ref "IC3") (pin "3") (pinfunction "C1-_3") (pintype "bidirectional"))
    )
    (net (code "29") (name "Net-(IC3A-C2+)") (class "Default")
      (node (ref "C4") (pin "1") (pinfunction "1_1") (pintype "passive"))
      (node (ref "IC3") (pin "4") (pinfunction "C2+_4") (pintype "bidirectional"))
    )
    (net (code "30") (name "Net-(IC3A-C2-)") (class "Default")
      (node (ref "C4") (pin "2") (pinfunction "2_2") (pintype "passive"))
      (node (ref "IC3") (pin "5") (pinfunction "C2-_5") (pintype "bidirectional"))
    )
    (net (code "31") (name "Net-(IC3A-R1OUT)") (class "Default")
      (node (ref "IC3") (pin "12") (pinfunction "R1OUT_12") (pintype "output"))
      (node (ref "R1") (pin "2") (pinfunction "2_2") (pintype "passive"))
    )
    (net (code "32") (name "Net-(IC3A-T1IN)") (class "Default")
      (node (ref "IC3") (pin "11") (pinfunction "T1IN_11") (pintype "input"))
      (node (ref "R8") (pin "2") (pinfunction "2_2") (pintype "passive"))
    )
    (net (code "33") (name "Net-(IC3A-V+)") (class "Default")
      (node (ref "C8") (pin "1") (pinfunction "1_1") (pintype "passive"))
      (node (ref "IC3") (pin "2") (pinfunction "V+_2") (pintype "bidirectional"))
    )
    (net (code "34") (name "Net-(IC3A-V-)") (class "Default")
      (node (ref "C6") (pin "1") (pinfunction "1_1") (pintype "passive"))
      (node (ref "IC3") (pin "6") (pinfunction "V-_6") (pintype "bidirectional"))
    )
    (net (code "35") (name "Net-(IC6B--IN)") (class "Default")
      (node (ref "IC6") (pin "6") (pinfunction "-IN_6") (pintype "input"))
      (node (ref "IC6") (pin "7") (pinfunction "OUT_7") (pintype "output"))
      (node (ref "R26") (pin "2") (pinfunction "2_2") (pintype "passive"))
    )
    (net (code "36") (name "Net-(Q1-G)") (class "Default")
      (node (ref "Q1") (pin "1") (pinfunction "G_1") (pintype "passive"))
      (node (ref "R2") (pin "2") (pinfunction "2_2") (pintype "passive"))
      (node (ref "R6") (pin "2") (pinfunction "2_2") (pintype "passive"))
    )
    (net (code "37") (name "Net-(Q2-G)") (class "Default")
      (node (ref "Q2") (pin "1") (pinfunction "G_1") (pintype "passive"))
      (node (ref "R3") (pin "2") (pinfunction "2_2") (pintype "passive"))
      (node (ref "R7") (pin "2") (pinfunction "2_2") (pintype "passive"))
    )
    (net (code "38") (name "Net-(Q3-G)") (class "Default")
      (node (ref "Q3") (pin "1") (pinfunction "G_1") (pintype "passive"))
      (node (ref "R29") (pin "2") (pinfunction "2_2") (pintype "passive"))
      (node (ref "R32") (pin "2") (pinfunction "2_2") (pintype "passive"))
    )
    (net (code "39") (name "Net-(Q4-G)") (class "Default")
      (node (ref "Q4") (pin "1") (pinfunction "G_1") (pintype "passive"))
      (node (ref "R30") (pin "2") (pinfunction "2_2") (pintype "passive"))
      (node (ref "R31") (pin "2") (pinfunction "2_2") (pintype "passive"))
    )
    (net (code "40") (name "Net-(Q5-D)") (class "Default")
      (node (ref "Q5") (pin "3") (pinfunction "D_3") (pintype "passive"))
      (node (ref "X5") (pin "GND") (pinfunction "GND_GND") (pintype "bidirectional"))
    )
    (net (code "41") (name "Net-(Q5-G)") (class "Default")
      (node (ref "Q5") (pin "1") (pinfunction "G_1") (pintype "passive"))
      (node (ref "R33") (pin "2") (pinfunction "2_2") (pintype "passive"))
      (node (ref "R34") (pin "2") (pinfunction "2_2") (pintype "passive"))
    )
    (net (code "42") (name "Net-(Q6-D)") (class "Default")
      (node (ref "Q6") (pin "3") (pinfunction "D_3") (pintype "passive"))
      (node (ref "U1") (pin "2") (pinfunction "IN-_2") (pintype "bidirectional"))
    )
    (net (code "43") (name "Net-(Q6-G)") (class "Default")
      (node (ref "Q6") (pin "1") (pinfunction "G_1") (pintype "passive"))
      (node (ref "R35") (pin "2") (pinfunction "2_2") (pintype "passive"))
      (node (ref "R36") (pin "2") (pinfunction "2_2") (pintype "passive"))
    )
    (net (code "44") (name "ROTOR_AC_SUPPLY") (class "Default")
      (node (ref "R34") (pin "1") (pinfunction "1_1") (pintype "passive"))
      (node (ref "X1") (pin "8") (pinfunction "TIMER7_8") (pintype "passive"))
    )
    (net (code "45") (name "ROT_E_DOWN") (class "Default")
      (node (ref "Q4") (pin "3") (pinfunction "D_3") (pintype "passive"))
      (node (ref "R37") (pin "1") (pinfunction "1_1") (pintype "passive"))
      (node (ref "R40") (pin "1") (pinfunction "1_1") (pintype "passive"))
      (node (ref "X4") (pin "7") (pinfunction "7_7") (pintype "passive"))
    )
    (net (code "46") (name "ROT_E_POSITION") (class "Default")
      (node (ref "R28") (pin "2") (pinfunction "2_2") (pintype "passive"))
      (node (ref "X4") (pin "1") (pinfunction "1_1") (pintype "passive"))
    )
    (net (code "47") (name "ROT_E_UP") (class "Default")
      (node (ref "Q3") (pin "3") (pinfunction "D_3") (pintype "passive"))
      (node (ref "R38") (pin "1") (pinfunction "1_1") (pintype "passive"))
      (node (ref "R39") (pin "1") (pinfunction "1_1") (pintype "passive"))
      (node (ref "X4") (pin "8") (pinfunction "8_8") (pintype "passive"))
    )
    (net (code "48") (name "ROT_H_LEFT") (class "Default")
      (node (ref "Q1") (pin "3") (pinfunction "D_3") (pintype "passive"))
      (node (ref "X4") (pin "3") (pinfunction "3_3") (pintype "passive"))
    )
    (net (code "49") (name "ROT_H_POSITON") (class "Default")
      (node (ref "R10") (pin "2") (pinfunction "2_2") (pintype "passive"))
      (node (ref "X4") (pin "5") (pinfunction "5_5") (pintype "passive"))
    )
    (net (code "50") (name "ROT_H_RIGHT") (class "Default")
      (node (ref "Q2") (pin "3") (pinfunction "D_3") (pintype "passive"))
      (node (ref "X4") (pin "2") (pinfunction "2_2") (pintype "passive"))
    )
    (net (code "51") (name "ROT_H_SPEED") (class "Default")
      (node (ref "R9") (pin "2") (pinfunction "2_2") (pintype "passive"))
      (node (ref "X4") (pin "4") (pinfunction "4_4") (pintype "passive"))
    )
    (net (code "52") (name "RS232_RX") (class "Default")
      (node (ref "IC3") (pin "13") (pinfunction "R1IN_13") (pintype "input"))
      (node (ref "X2") (pin "3") (pinfunction "3_3") (pintype "passive"))
    )
    (net (code "53") (name "RS232_TX") (class "Default")
      (node (ref "IC3") (pin "14") (pinfunction "T1OUT_14") (pintype "output"))
      (node (ref "X2") (pin "2") (pinfunction "2_2") (pintype "passive"))
    )
    (net (code "54") (name "SYS_5V") (class "Default")
      (node (ref "X1") (pin "53") (pinfunction "SYS_5V_53") (pintype "power_in"))
    )
    (net (code "55") (name "unconnected-(IC3A-R2IN-Pad8)") (class "Default")
      (node (ref "IC3") (pin "8") (pinfunction "R2IN_8") (pintype "input"))
    )
    (net (code "56") (name "unconnected-(IC3A-R2OUT-Pad9)") (class "Default")
      (node (ref "IC3") (pin "9") (pinfunction "R2OUT_9") (pintype "output"))
    )
    (net (code "57") (name "unconnected-(IC3A-T2IN-Pad10)") (class "Default")
      (node (ref "IC3") (pin "10") (pinfunction "T2IN_10") (pintype "input"))
    )
    (net (code "58") (name "unconnected-(IC3A-T2OUT-Pad7)") (class "Default")
      (node (ref "IC3") (pin "7") (pinfunction "T2OUT_7") (pintype "output"))
    )
    (net (code "59") (name "unconnected-(X1-AIN2-Pad83)") (class "Default")
      (node (ref "X1") (pin "83") (pinfunction "AIN2_83") (pintype "passive"))
    )
    (net (code "60") (name "unconnected-(X1-AIN4-Pad79)") (class "Default")
      (node (ref "X1") (pin "79") (pinfunction "AIN4_79") (pintype "passive"))
    )
    (net (code "61") (name "unconnected-(X1-AIN6-Pad81)") (class "Default")
      (node (ref "X1") (pin "81") (pinfunction "AIN6_81") (pintype "passive"))
    )
    (net (code "62") (name "unconnected-(X1-EHRPWM1A-Pad60)") (class "Default")
      (node (ref "X1") (pin "60") (pinfunction "EHRPWM1A_60") (pintype "passive"))
    )
    (net (code "63") (name "unconnected-(X1-EHRPWM1B-Pad62)") (class "Default")
      (node (ref "X1") (pin "62") (pinfunction "EHRPWM1B_62") (pintype "passive"))
    )
    (net (code "64") (name "unconnected-(X1-EHRPWM2A-Pad19)") (class "Default")
      (node (ref "X1") (pin "19") (pinfunction "EHRPWM2A_19") (pintype "passive"))
    )
    (net (code "65") (name "unconnected-(X1-GPIO0_26-Pad14)") (class "Default")
      (node (ref "X1") (pin "14") (pinfunction "GPIO0_26_14") (pintype "passive"))
    )
    (net (code "66") (name "unconnected-(X1-GPIO1_0-Pad25)") (class "Default")
      (node (ref "X1") (pin "25") (pinfunction "GPIO1_0_25") (pintype "passive"))
    )
    (net (code "67") (name "unconnected-(X1-GPIO1_1-Pad24)") (class "Default")
      (node (ref "X1") (pin "24") (pinfunction "GPIO1_1_24") (pintype "passive"))
    )
    (net (code "68") (name "unconnected-(X1-GPIO1_2-Pad5)") (class "Default")
      (node (ref "X1") (pin "5") (pinfunction "GPIO1_2_5") (pintype "passive"))
    )
    (net (code "69") (name "unconnected-(X1-GPIO1_3-Pad6)") (class "Default")
      (node (ref "X1") (pin "6") (pinfunction "GPIO1_3_6") (pintype "passive"))
    )
    (net (code "70") (name "unconnected-(X1-GPIO1_4-Pad23)") (class "Default")
      (node (ref "X1") (pin "23") (pinfunction "GPIO1_4_23") (pintype "passive"))
    )
    (net (code "71") (name "unconnected-(X1-GPIO1_5-Pad22)") (class "Default")
      (node (ref "X1") (pin "22") (pinfunction "GPIO1_5_22") (pintype "passive"))
    )
    (net (code "72") (name "unconnected-(X1-GPIO1_6-Pad3)") (class "Default")
      (node (ref "X1") (pin "3") (pinfunction "GPIO1_6_3") (pintype "passive"))
    )
    (net (code "73") (name "unconnected-(X1-GPIO1_7-Pad4)") (class "Default")
      (node (ref "X1") (pin "4") (pinfunction "GPIO1_7_4") (pintype "passive"))
    )
    (net (code "74") (name "unconnected-(X1-GPIO1_12-Pad12)") (class "Default")
      (node (ref "X1") (pin "12") (pinfunction "GPIO1_12_12") (pintype "passive"))
    )
    (net (code "75") (name "unconnected-(X1-GPIO1_14-Pad16)") (class "Default")
      (node (ref "X1") (pin "16") (pinfunction "GPIO1_14_16") (pintype "passive"))
    )
    (net (code "76") (name "unconnected-(X1-GPIO1_16-Pad61)") (class "Default")
      (node (ref "X1") (pin "61") (pinfunction "GPIO1_16_61") (pintype "passive"))
    )
    (net (code "77") (name "unconnected-(X1-GPIO1_17-Pad69)") (class "Default")
      (node (ref "X1") (pin "69") (pinfunction "GPIO1_17_69") (pintype "passive"))
    )
    (net (code "78") (name "unconnected-(X1-GPIO1_28-Pad58)") (class "Default")
      (node (ref "X1") (pin "58") (pinfunction "GPIO1_28_58") (pintype "passive"))
    )
    (net (code "79") (name "unconnected-(X1-GPIO1_30-Pad21)") (class "Default")
      (node (ref "X1") (pin "21") (pinfunction "GPIO1_30_21") (pintype "passive"))
    )
    (net (code "80") (name "unconnected-(X1-GPIO1_31-Pad20)") (class "Default")
      (node (ref "X1") (pin "20") (pinfunction "GPIO1_31_20") (pintype "passive"))
    )
    (net (code "81") (name "unconnected-(X1-GPIO2_1-Pad18)") (class "Default")
      (node (ref "X1") (pin "18") (pinfunction "GPIO2_1_18") (pintype "passive"))
    )
    (net (code "82") (name "unconnected-(X1-GPIO3_19-Pad73)") (class "Default")
      (node (ref "X1") (pin "73") (pinfunction "GPIO3_19_73") (pintype "passive"))
    )
    (net (code "83") (name "unconnected-(X1-GPIO3_21-Pad71)") (class "Default")
      (node (ref "X1") (pin "71") (pinfunction "GPIO3_21_71") (pintype "passive"))
    )
    (net (code "84") (name "unconnected-(X1-I2C1_SDA-Pad64)") (class "Default")
      (node (ref "X1") (pin "64") (pinfunction "I2C1_SDA_64") (pintype "passive"))
    )
    (net (code "85") (name "unconnected-(X1-I2C2_SCL-Pad65)") (class "Default")
      (node (ref "X1") (pin "65") (pinfunction "I2C2_SCL_65") (pintype "passive"))
    )
    (net (code "86") (name "unconnected-(X1-I2C2_SDA-Pad66)") (class "Default")
      (node (ref "X1") (pin "66") (pinfunction "I2C2_SDA_66") (pintype "passive"))
    )
    (net (code "87") (name "unconnected-(X1-PWR_BUT-Pad55)") (class "Default")
      (node (ref "X1") (pin "55") (pinfunction "PWR_BUT_55") (pintype "passive"))
    )
    (net (code "88") (name "unconnected-(X1-SPI1_CS0-Pad74)") (class "Default")
      (node (ref "X1") (pin "74") (pinfunction "SPI1_CS0_74") (pintype "passive"))
    )
    (net (code "89") (name "unconnected-(X1-SPI1_DI-Pad76)") (class "Default")
      (node (ref "X1") (pin "76") (pinfunction "SPI1_DI_76") (pintype "passive"))
    )
    (net (code "90") (name "unconnected-(X1-SPI1_DO-Pad75)") (class "Default")
      (node (ref "X1") (pin "75") (pinfunction "SPI1_DO_75") (pintype "passive"))
    )
    (net (code "91") (name "unconnected-(X1-SPI1_SCLK-Pad77)") (class "Default")
      (node (ref "X1") (pin "77") (pinfunction "SPI1_SCLK_77") (pintype "passive"))
    )
    (net (code "92") (name "unconnected-(X1-SYS_5V-Pad54)") (class "Default")
      (node (ref "X1") (pin "54") (pinfunction "SYS_5V_54") (pintype "passive"))
    )
    (net (code "93") (name "unconnected-(X1-SYS_RESETN-Pad56)") (class "Default")
      (node (ref "X1") (pin "56") (pinfunction "SYS_RESETN_56") (pintype "passive"))
    )
    (net (code "94") (name "unconnected-(X1-TIMER4-Pad7)") (class "Default")
      (node (ref "X1") (pin "7") (pinfunction "TIMER4_7") (pintype "passive"))
    )
    (net (code "95") (name "unconnected-(X1-TIMER5-Pad9)") (class "Default")
      (node (ref "X1") (pin "9") (pinfunction "TIMER5_9") (pintype "passive"))
    )
    (net (code "96") (name "unconnected-(X1-TIMER6-Pad10)") (class "Default")
      (node (ref "X1") (pin "10") (pinfunction "TIMER6_10") (pintype "passive"))
    )
    (net (code "97") (name "unconnected-(X1-UART1_RXD-Pad72)") (class "Default")
      (node (ref "X1") (pin "72") (pinfunction "UART1_RXD_72") (pintype "passive"))
    )
    (net (code "98") (name "unconnected-(X1-UART1_TXD-Pad70)") (class "Default")
      (node (ref "X1") (pin "70") (pinfunction "UART1_TXD_70") (pintype "passive"))
    )
    (net (code "99") (name "unconnected-(X1-VDD_ADC-Pad78)") (class "Default")
      (node (ref "X1") (pin "78") (pinfunction "VDD_ADC_78") (pintype "passive"))
    )
    (net (code "100") (name "unconnected-(X2-Pad1)") (class "Default")
      (node (ref "X2") (pin "1") (pinfunction "1_1") (pintype "passive"))
    )
    (net (code "101") (name "unconnected-(X2-Pad4)") (class "Default")
      (node (ref "X2") (pin "4") (pinfunction "4_4") (pintype "passive"))
    )
    (net (code "102") (name "unconnected-(X2-Pad6)") (class "Default")
      (node (ref "X2") (pin "6") (pinfunction "6_6") (pintype "passive"))
    )
    (net (code "103") (name "unconnected-(X2-Pad7)") (class "Default")
      (node (ref "X2") (pin "7") (pinfunction "7_7") (pintype "passive"))
    )
    (net (code "104") (name "unconnected-(X2-Pad8)") (class "Default")
      (node (ref "X2") (pin "8") (pinfunction "8_8") (pintype "passive"))
    )
    (net (code "105") (name "unconnected-(X2-Pad9)") (class "Default")
      (node (ref "X2") (pin "9") (pinfunction "9_9") (pintype "passive"))
    )
    (net (code "106") (name "unconnected-(X5-D+-Pad2-D+)") (class "Default")
      (node (ref "X5") (pin "2-D+") (pinfunction "D+_2-D+") (pintype "bidirectional"))
    )
    (net (code "107") (name "unconnected-(X5-D--Pad2-D-)") (class "Default")
      (node (ref "X5") (pin "2-D-") (pinfunction "D-_2-D-") (pintype "bidirectional"))
    )
  )
)
